# ZwiftCommand.net
KiCad netlist of a schematic drawn in EAGLE
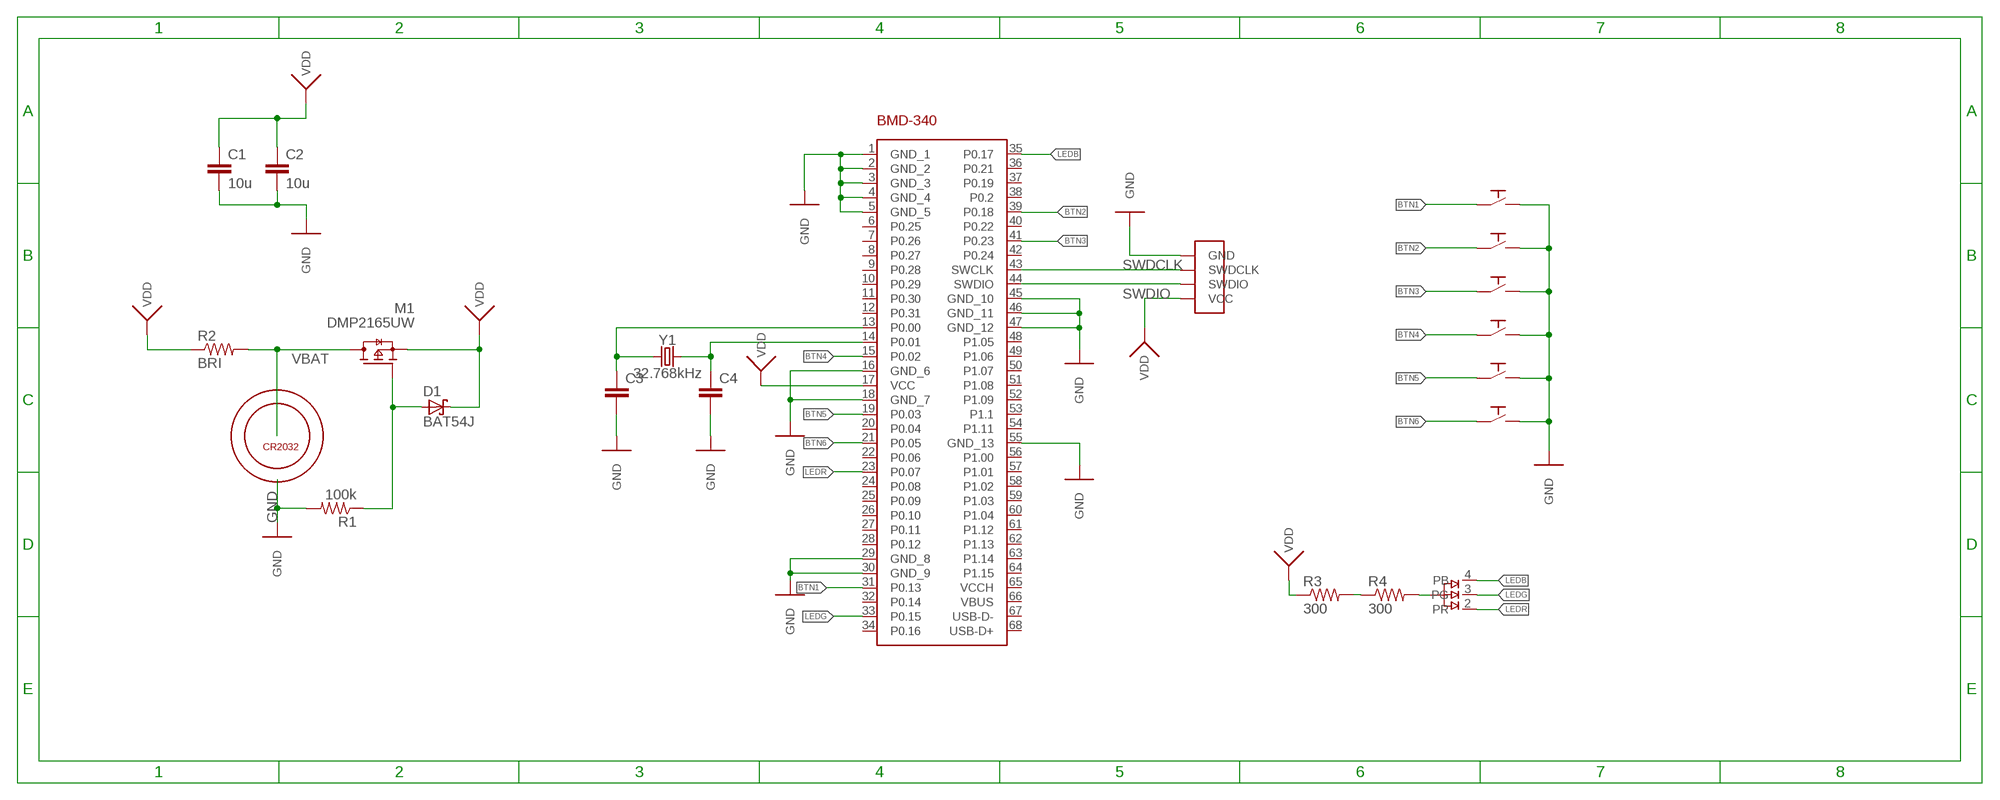
[diagram p0: schematic, sheet 1]

(export (version "E")
  (design (tool "Eeschema 10.0.6"))
  (components
    (comp (ref "C1")
      (value "10u")
      (footprint "eagle-import:C0603")
      (libsource (lib "eagle-import") (part "C-EUC0603"))
    )
    (comp (ref "C2")
      (value "10u")
      (footprint "eagle-import:C0603")
      (libsource (lib "eagle-import") (part "C-EUC0603"))
    )
    (comp (ref "C3")
      (value "C-EUC0603")
      (footprint "eagle-import:C0603")
      (libsource (lib "eagle-import") (part "C-EUC0603"))
    )
    (comp (ref "C4")
      (value "C-EUC0603")
      (footprint "eagle-import:C0603")
      (libsource (lib "eagle-import") (part "C-EUC0603"))
    )
    (comp (ref "D1")
      (value "BAT54J")
      (footprint "eagle-import:SOD323(F)")
      (libsource (lib "eagle-import") (part "BAT54J"))
    )
    (comp (ref "D2")
      (value "LRTBR48G")
      (footprint "eagle-import:LRTBR48GP9Q71R7S526NP68")
      (libsource (lib "eagle-import") (part "LRTBR48G"))
    )
    (comp (ref "IC1")
      (value "BMD-340-A-R")
      (footprint "eagle-import:BMD340AR")
      (fields (field (name "MOUSER_PART_NUMBER") "377-BMD-340-A-R"))
      (libsource (lib "eagle-import") (part "BMD-340-A-R"))
    )
    (comp (ref "M1")
      (value "DMP2165UW")
      (footprint "eagle-import:SOT65P210X110-3N")
      (libsource (lib "eagle-import") (part "DMP2165UW"))
    )
    (comp (ref "R1")
      (value "100k")
      (footprint "eagle-import:R0603")
      (libsource (lib "eagle-import") (part "R-US_R0603"))
    )
    (comp (ref "R2")
      (value "BRI")
      (footprint "eagle-import:R0402")
      (libsource (lib "eagle-import") (part "R-US_R0402"))
    )
    (comp (ref "R3")
      (value "300")
      (footprint "eagle-import:R0603")
      (libsource (lib "eagle-import") (part "R-US_R0603"))
    )
    (comp (ref "R4")
      (value "300")
      (footprint "eagle-import:R0603")
      (libsource (lib "eagle-import") (part "R-US_R0603"))
    )
    (comp (ref "SPST1")
      (value "PTS526SK08")
      (footprint "eagle-import:PTS526SKG15SMTR2LFS")
      (libsource (lib "eagle-import") (part "PTS526SK08"))
    )
    (comp (ref "SPST2")
      (value "PTS526SK08")
      (footprint "eagle-import:PTS526SKG15SMTR2LFS")
      (libsource (lib "eagle-import") (part "PTS526SK08"))
    )
    (comp (ref "SPST3")
      (value "PTS526SK08")
      (footprint "eagle-import:PTS526SKG15SMTR2LFS")
      (libsource (lib "eagle-import") (part "PTS526SK08"))
    )
    (comp (ref "SPST4")
      (value "PTS526SK08")
      (footprint "eagle-import:PTS526SKG15SMTR2LFS")
      (libsource (lib "eagle-import") (part "PTS526SK08"))
    )
    (comp (ref "SPST5")
      (value "PTS526SK08")
      (footprint "eagle-import:PTS526SKG15SMTR2LFS")
      (libsource (lib "eagle-import") (part "PTS526SK08"))
    )
    (comp (ref "SPST6")
      (value "PTS526SK08")
      (footprint "eagle-import:PTS526SKG15SMTR2LFS")
      (libsource (lib "eagle-import") (part "PTS526SK08"))
    )
    (comp (ref "U$2")
      (value "PROG_SMD")
      (footprint "eagle-import:PROG_SMD")
      (libsource (lib "eagle-import") (part "PROG_SMD"))
    )
    (comp (ref "U1")
      (value "BAT-HLD-001-THM")
      (footprint "eagle-import:BATHLD001THM")
      (fields (field (name "MOUSER_PART_NUMBER") "712-BAT-HLD-001-THM"))
      (libsource (lib "eagle-import") (part "BAT-HLD-001-THM"))
    )
    (comp (ref "Y1")
      (value "32.768kHz")
      (footprint "eagle-import:CRYSTAL-SMD-3.2X1.5MM")
      (libsource (lib "eagle-import") (part "CRYSTAL-32.768KHZSMD-3.2X1.5"))
    )
  )
  (nets
    (net (code "1") (name "/SWDCLK") (class "Default")
      (node (ref "IC1") (pin "43") (pinfunction "SWCLK_43") (pintype "bidirectional"))
      (node (ref "U$2") (pin "PIN1") (pinfunction "SWDCLK_PIN1") (pintype "bidirectional"))
    )
    (net (code "2") (name "/SWDIO") (class "Default")
      (node (ref "IC1") (pin "44") (pinfunction "SWDIO_44") (pintype "bidirectional"))
      (node (ref "U$2") (pin "PIN2") (pinfunction "SWDIO_PIN2") (pintype "bidirectional"))
    )
    (net (code "3") (name "/VBAT") (class "Default")
      (node (ref "M1") (pin "3") (pinfunction "D_3") (pintype "passive"))
      (node (ref "R2") (pin "2") (pinfunction "2_2") (pintype "passive"))
      (node (ref "U1") (pin "1") (pinfunction "+_1") (pintype "power_in"))
      (node (ref "U1") (pin "2") (pinfunction "+_2") (pintype "power_in"))
      (node (ref "U1") (pin "3") (pinfunction "+_3") (pintype "power_in"))
      (node (ref "U1") (pin "4") (pinfunction "+_4") (pintype "power_in"))
    )
    (net (code "4") (name "BTN1") (class "Default")
      (node (ref "IC1") (pin "31") (pinfunction "P0.13_31") (pintype "bidirectional"))
      (node (ref "SPST1") (pin "1") (pinfunction "P$1_1") (pintype "bidirectional"))
      (node (ref "SPST1") (pin "2") (pinfunction "P$1_2") (pintype "bidirectional"))
    )
    (net (code "5") (name "BTN2") (class "Default")
      (node (ref "IC1") (pin "39") (pinfunction "P0.18_39") (pintype "bidirectional"))
      (node (ref "SPST2") (pin "1") (pinfunction "P$1_1") (pintype "bidirectional"))
      (node (ref "SPST2") (pin "2") (pinfunction "P$1_2") (pintype "bidirectional"))
    )
    (net (code "6") (name "BTN3") (class "Default")
      (node (ref "IC1") (pin "41") (pinfunction "P0.23_41") (pintype "bidirectional"))
      (node (ref "SPST3") (pin "1") (pinfunction "P$1_1") (pintype "bidirectional"))
      (node (ref "SPST3") (pin "2") (pinfunction "P$1_2") (pintype "bidirectional"))
    )
    (net (code "7") (name "BTN4") (class "Default")
      (node (ref "IC1") (pin "15") (pinfunction "P0.02_15") (pintype "bidirectional"))
      (node (ref "SPST4") (pin "1") (pinfunction "P$1_1") (pintype "bidirectional"))
      (node (ref "SPST4") (pin "2") (pinfunction "P$1_2") (pintype "bidirectional"))
    )
    (net (code "8") (name "BTN5") (class "Default")
      (node (ref "IC1") (pin "19") (pinfunction "P0.03_19") (pintype "bidirectional"))
      (node (ref "SPST5") (pin "1") (pinfunction "P$1_1") (pintype "bidirectional"))
      (node (ref "SPST5") (pin "2") (pinfunction "P$1_2") (pintype "bidirectional"))
    )
    (net (code "9") (name "BTN6") (class "Default")
      (node (ref "IC1") (pin "21") (pinfunction "P0.05_21") (pintype "bidirectional"))
      (node (ref "SPST6") (pin "1") (pinfunction "P$1_1") (pintype "bidirectional"))
      (node (ref "SPST6") (pin "2") (pinfunction "P$1_2") (pintype "bidirectional"))
    )
    (net (code "10") (name "GND") (class "Default")
      (node (ref "C1") (pin "2") (pinfunction "2_2") (pintype "passive"))
      (node (ref "C2") (pin "2") (pinfunction "2_2") (pintype "passive"))
      (node (ref "C3") (pin "2") (pinfunction "2_2") (pintype "passive"))
      (node (ref "C4") (pin "2") (pinfunction "2_2") (pintype "passive"))
      (node (ref "IC1") (pin "1") (pinfunction "GND_1_1") (pintype "bidirectional"))
      (node (ref "IC1") (pin "16") (pinfunction "GND_6_16") (pintype "bidirectional"))
      (node (ref "IC1") (pin "18") (pinfunction "GND_7_18") (pintype "bidirectional"))
      (node (ref "IC1") (pin "2") (pinfunction "GND_2_2") (pintype "bidirectional"))
      (node (ref "IC1") (pin "29") (pinfunction "GND_8_29") (pintype "bidirectional"))
      (node (ref "IC1") (pin "3") (pinfunction "GND_3_3") (pintype "bidirectional"))
      (node (ref "IC1") (pin "30") (pinfunction "GND_9_30") (pintype "bidirectional"))
      (node (ref "IC1") (pin "4") (pinfunction "GND_4_4") (pintype "bidirectional"))
      (node (ref "IC1") (pin "45") (pinfunction "GND_10_45") (pintype "bidirectional"))
      (node (ref "IC1") (pin "46") (pinfunction "GND_11_46") (pintype "bidirectional"))
      (node (ref "IC1") (pin "47") (pinfunction "GND_12_47") (pintype "bidirectional"))
      (node (ref "IC1") (pin "5") (pinfunction "GND_5_5") (pintype "bidirectional"))
      (node (ref "IC1") (pin "55") (pinfunction "GND_13_55") (pintype "bidirectional"))
      (node (ref "R1") (pin "2") (pinfunction "2_2") (pintype "passive"))
      (node (ref "SPST1") (pin "3") (pinfunction "P$2_3") (pintype "bidirectional"))
      (node (ref "SPST1") (pin "4") (pinfunction "P$2_4") (pintype "bidirectional"))
      (node (ref "SPST2") (pin "3") (pinfunction "P$2_3") (pintype "bidirectional"))
      (node (ref "SPST2") (pin "4") (pinfunction "P$2_4") (pintype "bidirectional"))
      (node (ref "SPST3") (pin "3") (pinfunction "P$2_3") (pintype "bidirectional"))
      (node (ref "SPST3") (pin "4") (pinfunction "P$2_4") (pintype "bidirectional"))
      (node (ref "SPST4") (pin "3") (pinfunction "P$2_3") (pintype "bidirectional"))
      (node (ref "SPST4") (pin "4") (pinfunction "P$2_4") (pintype "bidirectional"))
      (node (ref "SPST5") (pin "3") (pinfunction "P$2_3") (pintype "bidirectional"))
      (node (ref "SPST5") (pin "4") (pinfunction "P$2_4") (pintype "bidirectional"))
      (node (ref "SPST6") (pin "3") (pinfunction "P$2_3") (pintype "bidirectional"))
      (node (ref "SPST6") (pin "4") (pinfunction "P$2_4") (pintype "bidirectional"))
      (node (ref "U$2") (pin "GND") (pinfunction "GND_GND") (pintype "bidirectional"))
      (node (ref "U1") (pin "5") (pinfunction "-_5") (pintype "power_in"))
    )
    (net (code "11") (name "LEDB") (class "Default")
      (node (ref "D2") (pin "4") (pinfunction "PB_4") (pintype "bidirectional"))
      (node (ref "IC1") (pin "35") (pinfunction "P0.17_35") (pintype "bidirectional"))
    )
    (net (code "12") (name "LEDG") (class "Default")
      (node (ref "D2") (pin "3") (pinfunction "PG_3") (pintype "bidirectional"))
      (node (ref "IC1") (pin "33") (pinfunction "P0.15_33") (pintype "bidirectional"))
    )
    (net (code "13") (name "LEDR") (class "Default")
      (node (ref "D2") (pin "2") (pinfunction "PR_2") (pintype "bidirectional"))
      (node (ref "IC1") (pin "23") (pinfunction "P0.07_23") (pintype "bidirectional"))
    )
    (net (code "14") (name "Net-(D1-A)") (class "Default")
      (node (ref "D1") (pin "2") (pinfunction "A_2") (pintype "passive"))
      (node (ref "M1") (pin "1") (pinfunction "G_1") (pintype "passive"))
      (node (ref "R1") (pin "1") (pinfunction "1_1") (pintype "passive"))
    )
    (net (code "15") (name "Net-(D2-P$1)") (class "Default")
      (node (ref "D2") (pin "1") (pinfunction "P$1_1") (pintype "bidirectional"))
      (node (ref "R4") (pin "2") (pinfunction "2_2") (pintype "passive"))
    )
    (net (code "16") (name "Net-(IC1-P0.00)") (class "Default")
      (node (ref "C3") (pin "1") (pinfunction "1_1") (pintype "passive"))
      (node (ref "IC1") (pin "13") (pinfunction "P0.00_13") (pintype "bidirectional"))
      (node (ref "Y1") (pin "P$1") (pinfunction "1_P$1") (pintype "passive"))
    )
    (net (code "17") (name "Net-(IC1-P0.01)") (class "Default")
      (node (ref "C4") (pin "1") (pinfunction "1_1") (pintype "passive"))
      (node (ref "IC1") (pin "14") (pinfunction "P0.01_14") (pintype "bidirectional"))
      (node (ref "Y1") (pin "P$2") (pinfunction "2_P$2") (pintype "passive"))
    )
    (net (code "18") (name "Net-(R3-Pad2)") (class "Default")
      (node (ref "R3") (pin "2") (pinfunction "2_2") (pintype "passive"))
      (node (ref "R4") (pin "1") (pinfunction "1_1") (pintype "passive"))
    )
    (net (code "19") (name "VDD") (class "Default")
      (node (ref "C1") (pin "1") (pinfunction "1_1") (pintype "passive"))
      (node (ref "C2") (pin "1") (pinfunction "1_1") (pintype "passive"))
      (node (ref "D1") (pin "1") (pinfunction "K_1") (pintype "passive"))
      (node (ref "IC1") (pin "17") (pinfunction "VCC_17") (pintype "bidirectional"))
      (node (ref "M1") (pin "2") (pinfunction "S_2") (pintype "passive"))
      (node (ref "R2") (pin "1") (pinfunction "1_1") (pintype "passive"))
      (node (ref "R3") (pin "1") (pinfunction "1_1") (pintype "passive"))
      (node (ref "U$2") (pin "VCC") (pinfunction "VCC_VCC") (pintype "bidirectional"))
    )
    (net (code "20") (name "unconnected-(IC1-P0.2-Pad38)") (class "Default")
      (node (ref "IC1") (pin "38") (pinfunction "P0.2_38") (pintype "bidirectional"))
    )
    (net (code "21") (name "unconnected-(IC1-P0.04-Pad20)") (class "Default")
      (node (ref "IC1") (pin "20") (pinfunction "P0.04_20") (pintype "bidirectional"))
    )
    (net (code "22") (name "unconnected-(IC1-P0.06-Pad22)") (class "Default")
      (node (ref "IC1") (pin "22") (pinfunction "P0.06_22") (pintype "bidirectional"))
    )
    (net (code "23") (name "unconnected-(IC1-P0.08-Pad24)") (class "Default")
      (node (ref "IC1") (pin "24") (pinfunction "P0.08_24") (pintype "bidirectional"))
    )
    (net (code "24") (name "unconnected-(IC1-P0.09-Pad25)") (class "Default")
      (node (ref "IC1") (pin "25") (pinfunction "P0.09_25") (pintype "bidirectional"))
    )
    (net (code "25") (name "unconnected-(IC1-P0.10-Pad26)") (class "Default")
      (node (ref "IC1") (pin "26") (pinfunction "P0.10_26") (pintype "bidirectional"))
    )
    (net (code "26") (name "unconnected-(IC1-P0.11-Pad27)") (class "Default")
      (node (ref "IC1") (pin "27") (pinfunction "P0.11_27") (pintype "bidirectional"))
    )
    (net (code "27") (name "unconnected-(IC1-P0.12-Pad28)") (class "Default")
      (node (ref "IC1") (pin "28") (pinfunction "P0.12_28") (pintype "bidirectional"))
    )
    (net (code "28") (name "unconnected-(IC1-P0.14-Pad32)") (class "Default")
      (node (ref "IC1") (pin "32") (pinfunction "P0.14_32") (pintype "bidirectional"))
    )
    (net (code "29") (name "unconnected-(IC1-P0.16-Pad34)") (class "Default")
      (node (ref "IC1") (pin "34") (pinfunction "P0.16_34") (pintype "bidirectional"))
    )
    (net (code "30") (name "unconnected-(IC1-P0.19-Pad37)") (class "Default")
      (node (ref "IC1") (pin "37") (pinfunction "P0.19_37") (pintype "bidirectional"))
    )
    (net (code "31") (name "unconnected-(IC1-P0.21-Pad36)") (class "Default")
      (node (ref "IC1") (pin "36") (pinfunction "P0.21_36") (pintype "bidirectional"))
    )
    (net (code "32") (name "unconnected-(IC1-P0.22-Pad40)") (class "Default")
      (node (ref "IC1") (pin "40") (pinfunction "P0.22_40") (pintype "bidirectional"))
    )
    (net (code "33") (name "unconnected-(IC1-P0.24-Pad42)") (class "Default")
      (node (ref "IC1") (pin "42") (pinfunction "P0.24_42") (pintype "bidirectional"))
    )
    (net (code "34") (name "unconnected-(IC1-P0.25-Pad6)") (class "Default")
      (node (ref "IC1") (pin "6") (pinfunction "P0.25_6") (pintype "bidirectional"))
    )
    (net (code "35") (name "unconnected-(IC1-P0.26-Pad7)") (class "Default")
      (node (ref "IC1") (pin "7") (pinfunction "P0.26_7") (pintype "bidirectional"))
    )
    (net (code "36") (name "unconnected-(IC1-P0.27-Pad8)") (class "Default")
      (node (ref "IC1") (pin "8") (pinfunction "P0.27_8") (pintype "bidirectional"))
    )
    (net (code "37") (name "unconnected-(IC1-P0.28-Pad9)") (class "Default")
      (node (ref "IC1") (pin "9") (pinfunction "P0.28_9") (pintype "bidirectional"))
    )
    (net (code "38") (name "unconnected-(IC1-P0.29-Pad10)") (class "Default")
      (node (ref "IC1") (pin "10") (pinfunction "P0.29_10") (pintype "bidirectional"))
    )
    (net (code "39") (name "unconnected-(IC1-P0.30-Pad11)") (class "Default")
      (node (ref "IC1") (pin "11") (pinfunction "P0.30_11") (pintype "bidirectional"))
    )
    (net (code "40") (name "unconnected-(IC1-P0.31-Pad12)") (class "Default")
      (node (ref "IC1") (pin "12") (pinfunction "P0.31_12") (pintype "bidirectional"))
    )
    (net (code "41") (name "unconnected-(IC1-P1.00-Pad56)") (class "Default")
      (node (ref "IC1") (pin "56") (pinfunction "P1.00_56") (pintype "bidirectional"))
    )
    (net (code "42") (name "unconnected-(IC1-P1.1-Pad53)") (class "Default")
      (node (ref "IC1") (pin "53") (pinfunction "P1.1_53") (pintype "bidirectional"))
    )
    (net (code "43") (name "unconnected-(IC1-P1.01-Pad57)") (class "Default")
      (node (ref "IC1") (pin "57") (pinfunction "P1.01_57") (pintype "bidirectional"))
    )
    (net (code "44") (name "unconnected-(IC1-P1.02-Pad58)") (class "Default")
      (node (ref "IC1") (pin "58") (pinfunction "P1.02_58") (pintype "bidirectional"))
    )
    (net (code "45") (name "unconnected-(IC1-P1.03-Pad59)") (class "Default")
      (node (ref "IC1") (pin "59") (pinfunction "P1.03_59") (pintype "bidirectional"))
    )
    (net (code "46") (name "unconnected-(IC1-P1.04-Pad60)") (class "Default")
      (node (ref "IC1") (pin "60") (pinfunction "P1.04_60") (pintype "bidirectional"))
    )
    (net (code "47") (name "unconnected-(IC1-P1.05-Pad48)") (class "Default")
      (node (ref "IC1") (pin "48") (pinfunction "P1.05_48") (pintype "bidirectional"))
    )
    (net (code "48") (name "unconnected-(IC1-P1.06-Pad49)") (class "Default")
      (node (ref "IC1") (pin "49") (pinfunction "P1.06_49") (pintype "bidirectional"))
    )
    (net (code "49") (name "unconnected-(IC1-P1.07-Pad50)") (class "Default")
      (node (ref "IC1") (pin "50") (pinfunction "P1.07_50") (pintype "bidirectional"))
    )
    (net (code "50") (name "unconnected-(IC1-P1.08-Pad51)") (class "Default")
      (node (ref "IC1") (pin "51") (pinfunction "P1.08_51") (pintype "bidirectional"))
    )
    (net (code "51") (name "unconnected-(IC1-P1.09-Pad52)") (class "Default")
      (node (ref "IC1") (pin "52") (pinfunction "P1.09_52") (pintype "bidirectional"))
    )
    (net (code "52") (name "unconnected-(IC1-P1.11-Pad54)") (class "Default")
      (node (ref "IC1") (pin "54") (pinfunction "P1.11_54") (pintype "bidirectional"))
    )
    (net (code "53") (name "unconnected-(IC1-P1.12-Pad61)") (class "Default")
      (node (ref "IC1") (pin "61") (pinfunction "P1.12_61") (pintype "bidirectional"))
    )
    (net (code "54") (name "unconnected-(IC1-P1.13-Pad62)") (class "Default")
      (node (ref "IC1") (pin "62") (pinfunction "P1.13_62") (pintype "bidirectional"))
    )
    (net (code "55") (name "unconnected-(IC1-P1.14-Pad63)") (class "Default")
      (node (ref "IC1") (pin "63") (pinfunction "P1.14_63") (pintype "bidirectional"))
    )
    (net (code "56") (name "unconnected-(IC1-P1.15-Pad64)") (class "Default")
      (node (ref "IC1") (pin "64") (pinfunction "P1.15_64") (pintype "bidirectional"))
    )
    (net (code "57") (name "unconnected-(IC1-USB-D+-Pad68)") (class "Default")
      (node (ref "IC1") (pin "68") (pinfunction "USB-D+_68") (pintype "bidirectional"))
    )
    (net (code "58") (name "unconnected-(IC1-USB-D--Pad67)") (class "Default")
      (node (ref "IC1") (pin "67") (pinfunction "USB-D-_67") (pintype "bidirectional"))
    )
    (net (code "59") (name "unconnected-(IC1-VBUS-Pad66)") (class "Default")
      (node (ref "IC1") (pin "66") (pinfunction "VBUS_66") (pintype "bidirectional"))
    )
    (net (code "60") (name "unconnected-(IC1-VCCH-Pad65)") (class "Default")
      (node (ref "IC1") (pin "65") (pinfunction "VCCH_65") (pintype "bidirectional"))
    )
  )
)
